# SPI_RPM_Sensor.net
KiCad netlist of a schematic drawn in EAGLE
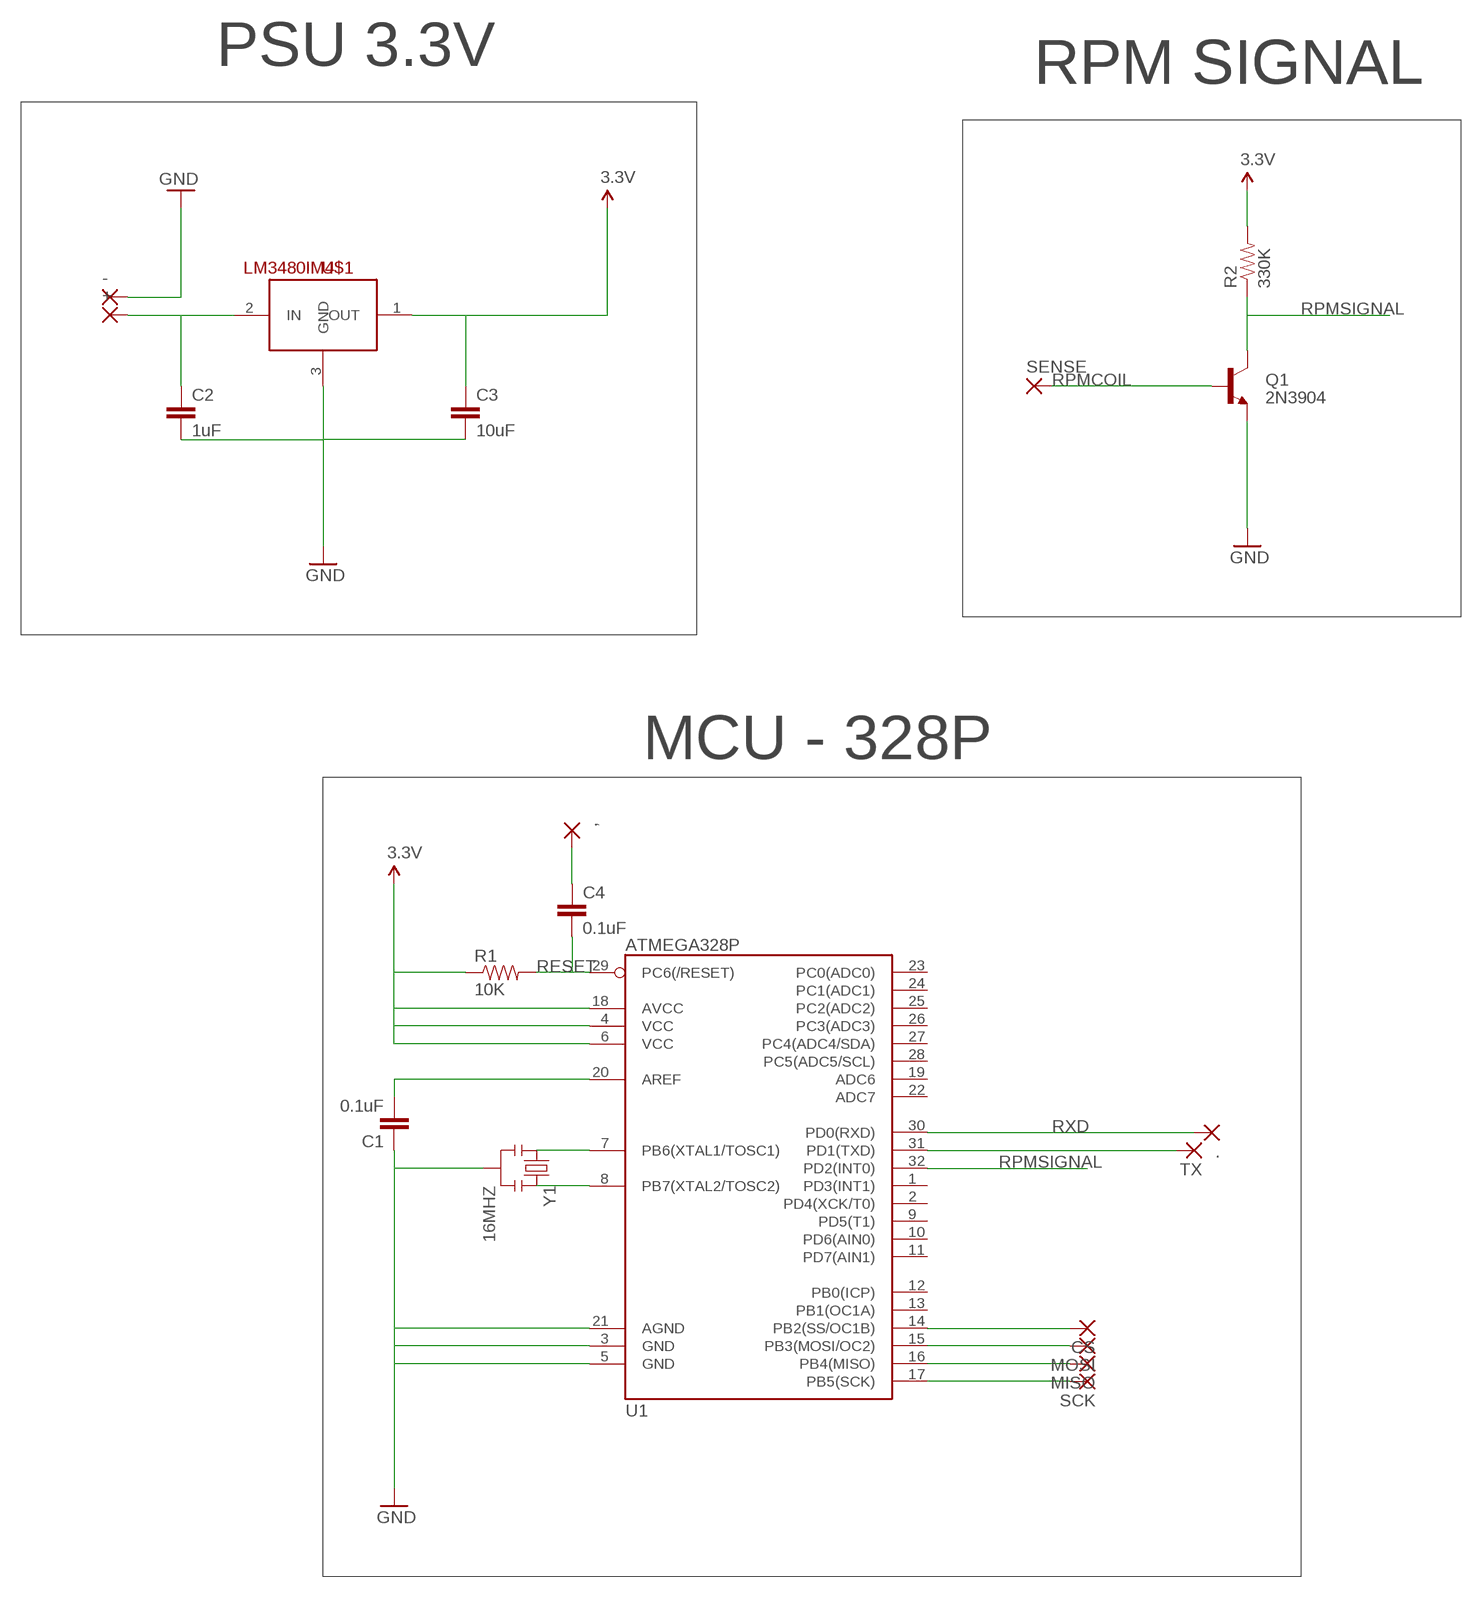
[diagram p0: schematic, sheet 1]

(export (version "E")
  (design (tool "Eeschema 10.0.6"))
  (components
    (comp (ref "+")
      (value "WIREPADSMD5-2,5")
      (footprint "eagle-import:5-2,5")
      (libsource (lib "eagle-import") (part "WIREPADSMD5-2,5"))
    )
    (comp (ref ",")
      (value "WIREPADSMD1,27-254")
      (footprint "eagle-import:SMD1,27-2,54")
      (libsource (lib "eagle-import") (part "WIREPADSMD1,27-254"))
    )
    (comp (ref "-")
      (value "WIREPADSMD5-2,5")
      (footprint "eagle-import:5-2,5")
      (libsource (lib "eagle-import") (part "WIREPADSMD5-2,5"))
    )
    (comp (ref ".")
      (value "WIREPADSMD1,27-254")
      (footprint "eagle-import:SMD1,27-2,54")
      (libsource (lib "eagle-import") (part "WIREPADSMD1,27-254"))
    )
    (comp (ref "C1")
      (value "0.1uF")
      (footprint "eagle-import:0603-CAP")
      (libsource (lib "eagle-import") (part "SparkFun-Passives_CAP0603-CAP"))
    )
    (comp (ref "C2")
      (value "1uF")
      (footprint "eagle-import:0603-CAP")
      (libsource (lib "eagle-import") (part "CAP0603-CAP"))
    )
    (comp (ref "C3")
      (value "10uF")
      (footprint "eagle-import:0603-CAP")
      (libsource (lib "eagle-import") (part "CAP0603-CAP"))
    )
    (comp (ref "C4")
      (value "0.1uF")
      (footprint "eagle-import:0603-CAP")
      (libsource (lib "eagle-import") (part "CAP0603-CAP"))
    )
    (comp (ref "CS")
      (value "WIREPADSMD5-2,5")
      (footprint "eagle-import:5-2,5")
      (libsource (lib "eagle-import") (part "WIREPADSMD5-2,5"))
    )
    (comp (ref "MISO")
      (value "WIREPADSMD5-2,5")
      (footprint "eagle-import:5-2,5")
      (libsource (lib "eagle-import") (part "WIREPADSMD5-2,5"))
    )
    (comp (ref "MOSI")
      (value "WIREPADSMD5-2,5")
      (footprint "eagle-import:5-2,5")
      (libsource (lib "eagle-import") (part "WIREPADSMD5-2,5"))
    )
    (comp (ref "Q1")
      (value "2N3904")
      (footprint "eagle-import:TO-92")
      (libsource (lib "eagle-import") (part "TRANSISTOR_NPN2N3904"))
    )
    (comp (ref "R1")
      (value "10K")
      (footprint "eagle-import:0603-RES")
      (libsource (lib "eagle-import") (part "RESISTOR0603"))
    )
    (comp (ref "R2")
      (value "330K")
      (footprint "eagle-import:0603-RES")
      (libsource (lib "eagle-import") (part "RESISTOR0603-RES"))
    )
    (comp (ref "SCK")
      (value "WIREPADSMD5-2,5")
      (footprint "eagle-import:5-2,5")
      (libsource (lib "eagle-import") (part "WIREPADSMD5-2,5"))
    )
    (comp (ref "SENSE")
      (value "WIREPADSMD5-2,5")
      (footprint "eagle-import:5-2,5")
      (libsource (lib "eagle-import") (part "WIREPADSMD5-2,5"))
    )
    (comp (ref "TX")
      (value "WIREPADSMD1,27-254")
      (footprint "eagle-import:SMD1,27-2,54")
      (libsource (lib "eagle-import") (part "WIREPADSMD1,27-254"))
    )
    (comp (ref "U$1")
      (value "LM3480IM4")
      (footprint "eagle-import:SOT23-3")
      (libsource (lib "eagle-import") (part "LM3480IM4"))
    )
    (comp (ref "U1")
      (value "ATMEGA328P")
      (footprint "eagle-import:TQFP32-08")
      (libsource (lib "eagle-import") (part "ATMEGA328_SMT"))
    )
    (comp (ref "Y1")
      (value "16MHZ")
      (footprint "eagle-import:RESONATOR-SMD")
      (libsource (lib "eagle-import") (part "RESONATOR16MHZ"))
    )
  )
  (nets
    (net (code "1") (name "/RESET") (class "Default")
      (node (ref "C4") (pin "2") (pinfunction "2_2") (pintype "passive"))
      (node (ref "R1") (pin "2") (pinfunction "2_2") (pintype "passive"))
      (node (ref "U1") (pin "29") (pinfunction "PC6(/RESET)_29") (pintype "bidirectional"))
    )
    (net (code "2") (name "/RPMCOIL") (class "Default")
      (node (ref "Q1") (pin "2") (pinfunction "B_2") (pintype "passive"))
      (node (ref "SENSE") (pin "1") (pinfunction "P_1") (pintype "passive"))
    )
    (net (code "3") (name "/RPMSIGNAL") (class "Default")
      (node (ref "Q1") (pin "3") (pinfunction "C_3") (pintype "passive"))
      (node (ref "R2") (pin "1") (pinfunction "1_1") (pintype "passive"))
      (node (ref "U1") (pin "32") (pinfunction "PD2(INT0)_32") (pintype "bidirectional"))
    )
    (net (code "4") (name "/RXD") (class "Default")
      (node (ref ".") (pin "1") (pinfunction "P_1") (pintype "passive"))
      (node (ref "U1") (pin "30") (pinfunction "PD0(RXD)_30") (pintype "bidirectional"))
    )
    (net (code "5") (name "3.3V") (class "Default")
      (node (ref "C3") (pin "1") (pinfunction "1_1") (pintype "passive"))
      (node (ref "R1") (pin "1") (pinfunction "1_1") (pintype "passive"))
      (node (ref "R2") (pin "2") (pinfunction "2_2") (pintype "passive"))
      (node (ref "U$1") (pin "1") (pinfunction "OUT_1") (pintype "bidirectional"))
      (node (ref "U1") (pin "18") (pinfunction "AVCC_18") (pintype "bidirectional"))
      (node (ref "U1") (pin "4") (pinfunction "VCC_4") (pintype "bidirectional"))
      (node (ref "U1") (pin "6") (pinfunction "VCC_6") (pintype "bidirectional"))
    )
    (net (code "6") (name "GND") (class "Default")
      (node (ref "-") (pin "1") (pinfunction "P_1") (pintype "passive"))
      (node (ref "C1") (pin "1") (pinfunction "1_1") (pintype "passive"))
      (node (ref "C2") (pin "2") (pinfunction "2_2") (pintype "passive"))
      (node (ref "C3") (pin "2") (pinfunction "2_2") (pintype "passive"))
      (node (ref "Q1") (pin "1") (pinfunction "E_1") (pintype "passive"))
      (node (ref "U$1") (pin "3") (pinfunction "GND_3") (pintype "bidirectional"))
      (node (ref "U1") (pin "21") (pinfunction "AGND_21") (pintype "bidirectional"))
      (node (ref "U1") (pin "3") (pinfunction "GND_3") (pintype "bidirectional"))
      (node (ref "U1") (pin "5") (pinfunction "GND_5") (pintype "bidirectional"))
      (node (ref "Y1") (pin "2") (pinfunction "2_2") (pintype "passive"))
    )
    (net (code "7") (name "Net-(+-P)") (class "Default")
      (node (ref "+") (pin "1") (pinfunction "P_1") (pintype "passive"))
      (node (ref "C2") (pin "1") (pinfunction "1_1") (pintype "passive"))
      (node (ref "U$1") (pin "2") (pinfunction "IN_2") (pintype "bidirectional"))
    )
    (net (code "8") (name "Net-(,-P)") (class "Default")
      (node (ref ",") (pin "1") (pinfunction "P_1") (pintype "passive"))
      (node (ref "C4") (pin "1") (pinfunction "1_1") (pintype "passive"))
    )
    (net (code "9") (name "Net-(CS-P)") (class "Default")
      (node (ref "CS") (pin "1") (pinfunction "P_1") (pintype "passive"))
      (node (ref "U1") (pin "14") (pinfunction "PB2(SS/OC1B)_14") (pintype "bidirectional"))
    )
    (net (code "10") (name "Net-(MISO-P)") (class "Default")
      (node (ref "MISO") (pin "1") (pinfunction "P_1") (pintype "passive"))
      (node (ref "U1") (pin "16") (pinfunction "PB4(MISO)_16") (pintype "bidirectional"))
    )
    (net (code "11") (name "Net-(MOSI-P)") (class "Default")
      (node (ref "MOSI") (pin "1") (pinfunction "P_1") (pintype "passive"))
      (node (ref "U1") (pin "15") (pinfunction "PB3(MOSI/OC2)_15") (pintype "bidirectional"))
    )
    (net (code "12") (name "Net-(SCK-P)") (class "Default")
      (node (ref "SCK") (pin "1") (pinfunction "P_1") (pintype "passive"))
      (node (ref "U1") (pin "17") (pinfunction "PB5(SCK)_17") (pintype "bidirectional"))
    )
    (net (code "13") (name "Net-(TX-P)") (class "Default")
      (node (ref "TX") (pin "1") (pinfunction "P_1") (pintype "passive"))
      (node (ref "U1") (pin "31") (pinfunction "PD1(TXD)_31") (pintype "bidirectional"))
    )
    (net (code "14") (name "Net-(U1-AREF)") (class "Default")
      (node (ref "C1") (pin "2") (pinfunction "2_2") (pintype "passive"))
      (node (ref "U1") (pin "20") (pinfunction "AREF_20") (pintype "bidirectional"))
    )
    (net (code "15") (name "Net-(U1-PB6(XTAL1{slash}TOSC1))") (class "Default")
      (node (ref "U1") (pin "7") (pinfunction "PB6(XTAL1/TOSC1)_7") (pintype "bidirectional"))
      (node (ref "Y1") (pin "1") (pinfunction "1_1") (pintype "passive"))
    )
    (net (code "16") (name "Net-(U1-PB7(XTAL2{slash}TOSC2))") (class "Default")
      (node (ref "U1") (pin "8") (pinfunction "PB7(XTAL2/TOSC2)_8") (pintype "bidirectional"))
      (node (ref "Y1") (pin "3") (pinfunction "3_3") (pintype "passive"))
    )
    (net (code "17") (name "unconnected-(U1-ADC6-Pad19)") (class "Default")
      (node (ref "U1") (pin "19") (pinfunction "ADC6_19") (pintype "bidirectional"))
    )
    (net (code "18") (name "unconnected-(U1-ADC7-Pad22)") (class "Default")
      (node (ref "U1") (pin "22") (pinfunction "ADC7_22") (pintype "bidirectional"))
    )
    (net (code "19") (name "unconnected-(U1-PB0(ICP)-Pad12)") (class "Default")
      (node (ref "U1") (pin "12") (pinfunction "PB0(ICP)_12") (pintype "bidirectional"))
    )
    (net (code "20") (name "unconnected-(U1-PB1(OC1A)-Pad13)") (class "Default")
      (node (ref "U1") (pin "13") (pinfunction "PB1(OC1A)_13") (pintype "bidirectional"))
    )
    (net (code "21") (name "unconnected-(U1-PC0(ADC0)-Pad23)") (class "Default")
      (node (ref "U1") (pin "23") (pinfunction "PC0(ADC0)_23") (pintype "bidirectional"))
    )
    (net (code "22") (name "unconnected-(U1-PC1(ADC1)-Pad24)") (class "Default")
      (node (ref "U1") (pin "24") (pinfunction "PC1(ADC1)_24") (pintype "bidirectional"))
    )
    (net (code "23") (name "unconnected-(U1-PC2(ADC2)-Pad25)") (class "Default")
      (node (ref "U1") (pin "25") (pinfunction "PC2(ADC2)_25") (pintype "bidirectional"))
    )
    (net (code "24") (name "unconnected-(U1-PC3(ADC3)-Pad26)") (class "Default")
      (node (ref "U1") (pin "26") (pinfunction "PC3(ADC3)_26") (pintype "bidirectional"))
    )
    (net (code "25") (name "unconnected-(U1-PC4(ADC4{slash}SDA)-Pad27)") (class "Default")
      (node (ref "U1") (pin "27") (pinfunction "PC4(ADC4/SDA)_27") (pintype "bidirectional"))
    )
    (net (code "26") (name "unconnected-(U1-PC5(ADC5{slash}SCL)-Pad28)") (class "Default")
      (node (ref "U1") (pin "28") (pinfunction "PC5(ADC5/SCL)_28") (pintype "bidirectional"))
    )
    (net (code "27") (name "unconnected-(U1-PD3(INT1)-Pad1)") (class "Default")
      (node (ref "U1") (pin "1") (pinfunction "PD3(INT1)_1") (pintype "bidirectional"))
    )
    (net (code "28") (name "unconnected-(U1-PD4(XCK{slash}T0)-Pad2)") (class "Default")
      (node (ref "U1") (pin "2") (pinfunction "PD4(XCK/T0)_2") (pintype "bidirectional"))
    )
    (net (code "29") (name "unconnected-(U1-PD5(T1)-Pad9)") (class "Default")
      (node (ref "U1") (pin "9") (pinfunction "PD5(T1)_9") (pintype "bidirectional"))
    )
    (net (code "30") (name "unconnected-(U1-PD6(AIN0)-Pad10)") (class "Default")
      (node (ref "U1") (pin "10") (pinfunction "PD6(AIN0)_10") (pintype "bidirectional"))
    )
    (net (code "31") (name "unconnected-(U1-PD7(AIN1)-Pad11)") (class "Default")
      (node (ref "U1") (pin "11") (pinfunction "PD7(AIN1)_11") (pintype "bidirectional"))
    )
  )
)
